# MRF24_Module.net
KiCad netlist of a schematic drawn in EAGLE
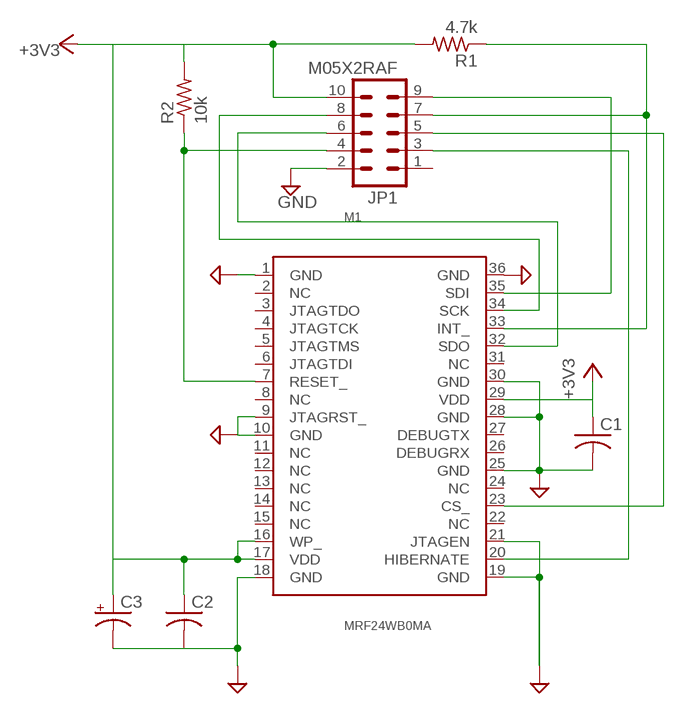
[diagram p0: schematic, sheet 1]

(export (version "E")
  (design (tool "Eeschema 10.0.6"))
  (components
    (comp (ref "C1")
      (value "C-USC0805")
      (footprint "eagle-import:C0805")
      (libsource (lib "eagle-import") (part "C-USC0805"))
    )
    (comp (ref "C2")
      (value "C-USC0805")
      (footprint "eagle-import:C0805")
      (libsource (lib "eagle-import") (part "C-USC0805"))
    )
    (comp (ref "C3")
      (value "CPOL-USR/2012-12R")
      (footprint "eagle-import:R_2012-12R")
      (libsource (lib "eagle-import") (part "CPOL-USR/2012-12R"))
    )
    (comp (ref "JP1")
      (value "M05X2RAF")
      (footprint "eagle-import:2X5-RAF")
      (libsource (lib "eagle-import") (part "M05X2RAF"))
    )
    (comp (ref "M1")
      (value "MRF24WB0MA")
      (footprint "eagle-import:MRF24W")
      (libsource (lib "eagle-import") (part "MR24WB0MA"))
    )
    (comp (ref "R1")
      (value "4.7k")
      (footprint "eagle-import:R0603")
      (libsource (lib "eagle-import") (part "R-US_R0603"))
    )
    (comp (ref "R2")
      (value "10k")
      (footprint "eagle-import:R0603")
      (libsource (lib "eagle-import") (part "R-US_R0603"))
    )
  )
  (nets
    (net (code "1") (name "+3V3") (class "Default")
      (node (ref "C1") (pin "1") (pinfunction "1_1") (pintype "passive"))
      (node (ref "C2") (pin "1") (pinfunction "1_1") (pintype "passive"))
      (node (ref "C3") (pin "+") (pinfunction "+_+") (pintype "passive"))
      (node (ref "JP1") (pin "10") (pinfunction "10_10") (pintype "passive"))
      (node (ref "M1") (pin "16") (pinfunction "WP__16") (pintype "bidirectional"))
      (node (ref "M1") (pin "17") (pinfunction "VDD_17") (pintype "bidirectional"))
      (node (ref "M1") (pin "29") (pinfunction "VDD_29") (pintype "bidirectional"))
      (node (ref "R1") (pin "2") (pinfunction "2_2") (pintype "passive"))
      (node (ref "R2") (pin "2") (pinfunction "2_2") (pintype "passive"))
    )
    (net (code "2") (name "GND") (class "Default")
      (node (ref "C1") (pin "2") (pinfunction "2_2") (pintype "passive"))
      (node (ref "C2") (pin "2") (pinfunction "2_2") (pintype "passive"))
      (node (ref "C3") (pin "-") (pinfunction "-_-") (pintype "passive"))
      (node (ref "JP1") (pin "2") (pinfunction "2_2") (pintype "passive"))
      (node (ref "M1") (pin "1") (pinfunction "GND_1") (pintype "bidirectional"))
      (node (ref "M1") (pin "10") (pinfunction "GND_10") (pintype "bidirectional"))
      (node (ref "M1") (pin "18") (pinfunction "GND_18") (pintype "bidirectional"))
      (node (ref "M1") (pin "19") (pinfunction "GND_19") (pintype "bidirectional"))
      (node (ref "M1") (pin "21") (pinfunction "JTAGEN_21") (pintype "bidirectional"))
      (node (ref "M1") (pin "25") (pinfunction "GND_25") (pintype "bidirectional"))
      (node (ref "M1") (pin "28") (pinfunction "GND_28") (pintype "bidirectional"))
      (node (ref "M1") (pin "30") (pinfunction "GND_30") (pintype "bidirectional"))
      (node (ref "M1") (pin "36") (pinfunction "GND_36") (pintype "bidirectional"))
      (node (ref "M1") (pin "9") (pinfunction "JTAGRST__9") (pintype "bidirectional"))
    )
    (net (code "3") (name "Net-(M1-CS_)") (class "Default")
      (node (ref "JP1") (pin "5") (pinfunction "5_5") (pintype "passive"))
      (node (ref "M1") (pin "23") (pinfunction "CS__23") (pintype "bidirectional"))
    )
    (net (code "4") (name "Net-(M1-HIBERNATE)") (class "Default")
      (node (ref "JP1") (pin "3") (pinfunction "3_3") (pintype "passive"))
      (node (ref "M1") (pin "20") (pinfunction "HIBERNATE_20") (pintype "bidirectional"))
    )
    (net (code "5") (name "Net-(M1-INT_)") (class "Default")
      (node (ref "JP1") (pin "7") (pinfunction "7_7") (pintype "passive"))
      (node (ref "M1") (pin "33") (pinfunction "INT__33") (pintype "bidirectional"))
      (node (ref "R1") (pin "1") (pinfunction "1_1") (pintype "passive"))
    )
    (net (code "6") (name "Net-(M1-RESET_)") (class "Default")
      (node (ref "JP1") (pin "4") (pinfunction "4_4") (pintype "passive"))
      (node (ref "M1") (pin "7") (pinfunction "RESET__7") (pintype "bidirectional"))
      (node (ref "R2") (pin "1") (pinfunction "1_1") (pintype "passive"))
    )
    (net (code "7") (name "Net-(M1-SCK)") (class "Default")
      (node (ref "JP1") (pin "8") (pinfunction "8_8") (pintype "passive"))
      (node (ref "M1") (pin "34") (pinfunction "SCK_34") (pintype "bidirectional"))
    )
    (net (code "8") (name "Net-(M1-SDI)") (class "Default")
      (node (ref "JP1") (pin "9") (pinfunction "9_9") (pintype "passive"))
      (node (ref "M1") (pin "35") (pinfunction "SDI_35") (pintype "bidirectional"))
    )
    (net (code "9") (name "Net-(M1-SDO)") (class "Default")
      (node (ref "JP1") (pin "6") (pinfunction "6_6") (pintype "passive"))
      (node (ref "M1") (pin "32") (pinfunction "SDO_32") (pintype "bidirectional"))
    )
    (net (code "10") (name "unconnected-(JP1-Pad1)") (class "Default")
      (node (ref "JP1") (pin "1") (pinfunction "1_1") (pintype "passive"))
    )
    (net (code "11") (name "unconnected-(M1-DEBUGRX-Pad26)") (class "Default")
      (node (ref "M1") (pin "26") (pinfunction "DEBUGRX_26") (pintype "bidirectional"))
    )
    (net (code "12") (name "unconnected-(M1-DEBUGTX-Pad27)") (class "Default")
      (node (ref "M1") (pin "27") (pinfunction "DEBUGTX_27") (pintype "bidirectional"))
    )
    (net (code "13") (name "unconnected-(M1-JTAGTCK-Pad4)") (class "Default")
      (node (ref "M1") (pin "4") (pinfunction "JTAGTCK_4") (pintype "bidirectional"))
    )
    (net (code "14") (name "unconnected-(M1-JTAGTDI-Pad6)") (class "Default")
      (node (ref "M1") (pin "6") (pinfunction "JTAGTDI_6") (pintype "bidirectional"))
    )
    (net (code "15") (name "unconnected-(M1-JTAGTDO-Pad3)") (class "Default")
      (node (ref "M1") (pin "3") (pinfunction "JTAGTDO_3") (pintype "bidirectional"))
    )
    (net (code "16") (name "unconnected-(M1-JTAGTMS-Pad5)") (class "Default")
      (node (ref "M1") (pin "5") (pinfunction "JTAGTMS_5") (pintype "bidirectional"))
    )
    (net (code "17") (name "unconnected-(M1-NC-Pad2)") (class "Default")
      (node (ref "M1") (pin "2") (pinfunction "NC_2") (pintype "bidirectional"))
    )
    (net (code "18") (name "unconnected-(M1-NC-Pad8)") (class "Default")
      (node (ref "M1") (pin "8") (pinfunction "NC_8") (pintype "bidirectional"))
    )
    (net (code "19") (name "unconnected-(M1-NC-Pad11)") (class "Default")
      (node (ref "M1") (pin "11") (pinfunction "NC_11") (pintype "bidirectional"))
    )
    (net (code "20") (name "unconnected-(M1-NC-Pad12)") (class "Default")
      (node (ref "M1") (pin "12") (pinfunction "NC_12") (pintype "bidirectional"))
    )
    (net (code "21") (name "unconnected-(M1-NC-Pad13)") (class "Default")
      (node (ref "M1") (pin "13") (pinfunction "NC_13") (pintype "bidirectional"))
    )
    (net (code "22") (name "unconnected-(M1-NC-Pad14)") (class "Default")
      (node (ref "M1") (pin "14") (pinfunction "NC_14") (pintype "bidirectional"))
    )
    (net (code "23") (name "unconnected-(M1-NC-Pad15)") (class "Default")
      (node (ref "M1") (pin "15") (pinfunction "NC_15") (pintype "bidirectional"))
    )
    (net (code "24") (name "unconnected-(M1-NC-Pad22)") (class "Default")
      (node (ref "M1") (pin "22") (pinfunction "NC_22") (pintype "bidirectional"))
    )
    (net (code "25") (name "unconnected-(M1-NC-Pad24)") (class "Default")
      (node (ref "M1") (pin "24") (pinfunction "NC_24") (pintype "bidirectional"))
    )
    (net (code "26") (name "unconnected-(M1-NC-Pad31)") (class "Default")
      (node (ref "M1") (pin "31") (pinfunction "NC_31") (pintype "bidirectional"))
    )
  )
)
